# STM32F103xx_LQFP48.net
KiCad netlist of a schematic drawn in Altium Designer
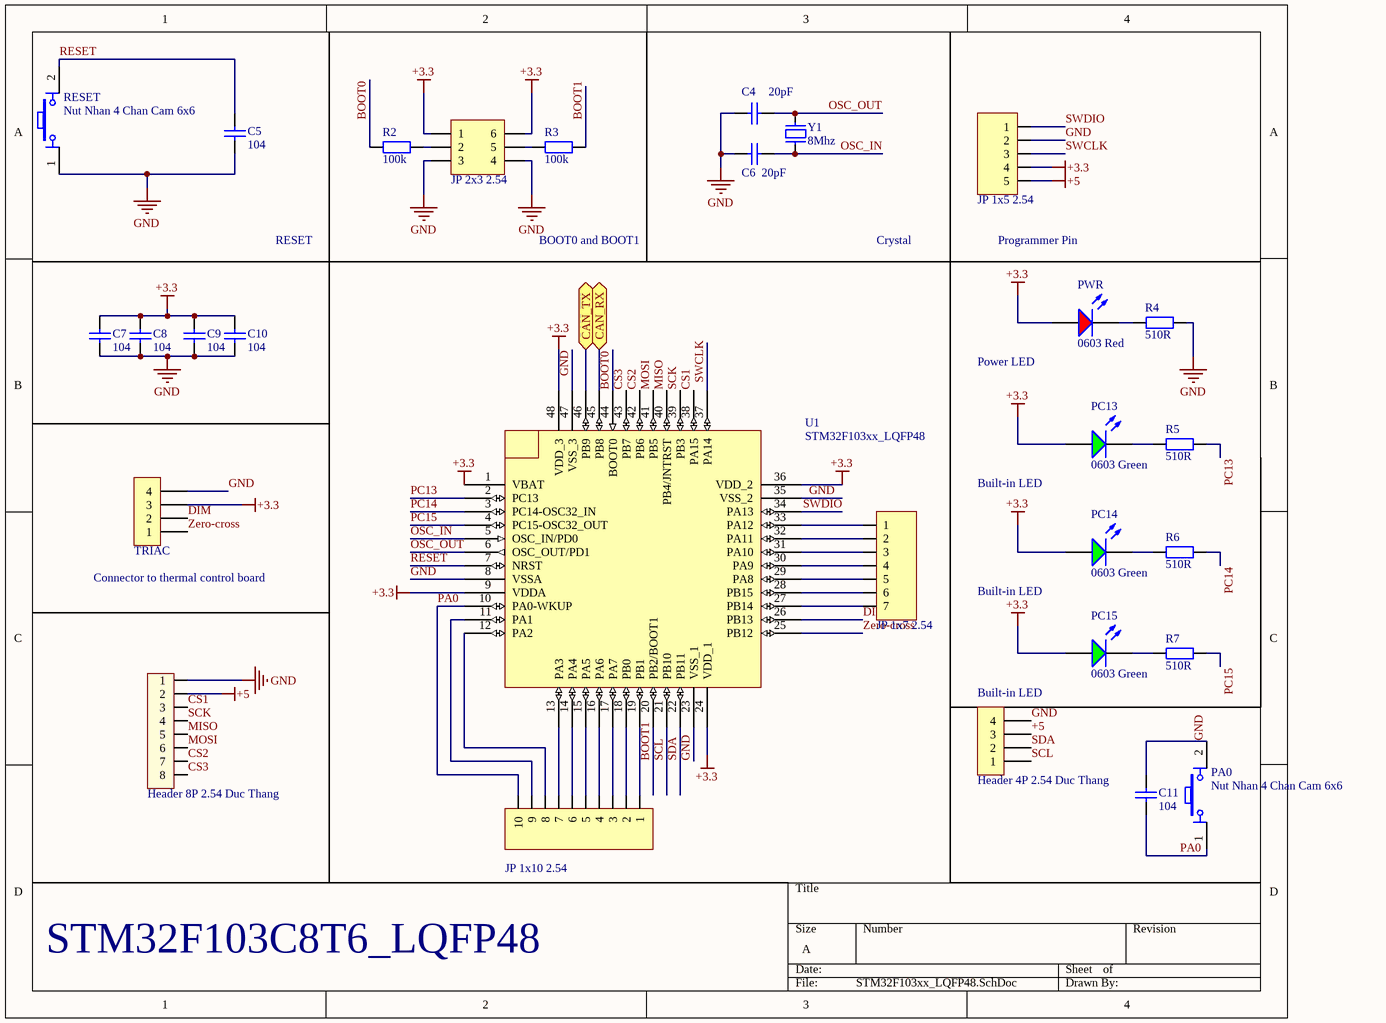
[diagram p0: STM32F103xx_LQFP48.SchDoc]

(export (version "E")
  (design (tool "Eeschema 10.0.6"))
  (components
    (comp (ref "C4")
      (value "20pF")
      (footprint "tu 0603")
      (description "Dán")
      (libsource (lib "Altium_Lib_by_KhueNguyenCreator") (part "Tu 0603 22pF 50V 10%"))
    )
    (comp (ref "C5")
      (value "104")
      (footprint "tu 0603")
      (description "Dán")
      (libsource (lib "Altium_Lib_by_KhueNguyenCreator") (part "Tu 0603 104 50V 10%"))
    )
    (comp (ref "C6")
      (value "20pF")
      (footprint "tu 0603")
      (description "Dán")
      (libsource (lib "Altium_Lib_by_KhueNguyenCreator") (part "Tu 0603 22pF 50V 10%"))
    )
    (comp (ref "C7")
      (value "104")
      (footprint "tu 0603")
      (description "Dán")
      (libsource (lib "Altium_Lib_by_KhueNguyenCreator") (part "Tu 0603 104 50V 10%"))
    )
    (comp (ref "C8")
      (value "104")
      (footprint "tu 0603")
      (description "Dán")
      (libsource (lib "Altium_Lib_by_KhueNguyenCreator") (part "Tu 0603 104 50V 10%"))
    )
    (comp (ref "C9")
      (value "104")
      (footprint "tu 0603")
      (description "Dán")
      (libsource (lib "Altium_Lib_by_KhueNguyenCreator") (part "Tu 0603 104 50V 10%"))
    )
    (comp (ref "C10")
      (value "104")
      (footprint "tu 0603")
      (description "Dán")
      (libsource (lib "Altium_Lib_by_KhueNguyenCreator") (part "Tu 0603 104 50V 10%"))
    )
    (comp (ref "C11")
      (value "104")
      (footprint "tu 0603")
      (description "Dán")
      (libsource (lib "Altium_Lib_by_KhueNguyenCreator") (part "Tu 0603 104 50V 10%"))
    )
    (comp (ref "H3")
      (value "TRIAC")
      (footprint "XH2.54M-4")
      (description "Cắm")
      (libsource (lib "Altium_Lib_by_KhueNguyenCreator") (part "Header 4P 2.54 Duc Thang"))
    )
    (comp (ref "H4")
      (value "Header 8P 2.54 Duc Thang")
      (footprint "XH2.54M-8")
      (description "Cắm")
      (libsource (lib "Altium_Lib_by_KhueNguyenCreator") (part "Header 8P 2.54 Duc Thang"))
    )
    (comp (ref "H5")
      (value "Header 4P 2.54 Duc Thang")
      (footprint "XH2.54M-4")
      (description "Cắm")
      (libsource (lib "Altium_Lib_by_KhueNguyenCreator") (part "Header 4P 2.54 Duc Thang"))
    )
    (comp (ref "JP2")
      (value "JP 1x5 2.54")
      (footprint "JP 1x5 DC")
      (description "Cắm")
      (libsource (lib "Altium_Lib_by_KhueNguyenCreator") (part "JP 1x5 2.54 Duc Cong"))
    )
    (comp (ref "JP3")
      (value "JP 2x3 2.54")
      (footprint "JP 2x3 DT")
      (description "Cắm")
      (libsource (lib "Altium_Lib_by_KhueNguyenCreator") (part "JP 2x3 2.54 Duc Thang"))
    )
    (comp (ref "JP4")
      (value "JP 1x7 2.54")
      (footprint "JP 1x7 DT")
      (description "Cắm")
      (libsource (lib "Altium_Lib_by_KhueNguyenCreator") (part "JP 1x7 2.54 Duc Thang"))
    )
    (comp (ref "JP5")
      (value "JP 1x10 2.54")
      (footprint "JP 1x10 DT")
      (description "Cắm")
      (libsource (lib "Altium_Lib_by_KhueNguyenCreator") (part "JP 1x10 2.54 Duc Thang"))
    )
    (comp (ref "PA0")
      (value "Nut Nhan 4 Chan Cam 6x6")
      (footprint "Nut Nhan 4 Chan Cam 6x6")
      (description "Nut Nhan 4 Chan 6x6mm")
      (libsource (lib "Altium_Lib_by_KhueNguyenCreator") (part "Nut Nhan 4 Chan Cam 6x6"))
    )
    (comp (ref "PC13")
      (value "0603 Green")
      (footprint "0603_LED_S1")
      (description "LED")
      (libsource (lib "Miscellaneous Devices LC") (part "0603 LED Green"))
    )
    (comp (ref "PC14")
      (value "0603 Green")
      (footprint "0603_LED_S1")
      (description "LED")
      (libsource (lib "Miscellaneous Devices LC") (part "0603 LED Green"))
    )
    (comp (ref "PC15")
      (value "0603 Green")
      (footprint "0603_LED_S1")
      (description "LED")
      (libsource (lib "Miscellaneous Devices LC") (part "0603 LED Green"))
    )
    (comp (ref "PWR")
      (value "0603 Red")
      (footprint "0603_LED_S1")
      (description "LED")
      (libsource (lib "Miscellaneous Devices LC") (part "0603 LED Red"))
    )
    (comp (ref "R2")
      (value "100k")
      (footprint "tro smd 0603")
      (description "Dán")
      (libsource (lib "Altium_Lib_by_KhueNguyenCreator") (part "Tro 0603 1% 10k"))
    )
    (comp (ref "R3")
      (value "100k")
      (footprint "tro smd 0603")
      (description "Dán")
      (libsource (lib "Altium_Lib_by_KhueNguyenCreator") (part "Tro 0603 1% 10k"))
    )
    (comp (ref "R4")
      (value "510R")
      (footprint "tro smd 0603")
      (description "Dán")
      (libsource (lib "Altium_Lib_by_KhueNguyenCreator") (part "Tro 0603 1% 10k"))
    )
    (comp (ref "R5")
      (value "510R")
      (footprint "tro smd 0603")
      (description "Dán")
      (libsource (lib "Altium_Lib_by_KhueNguyenCreator") (part "Tro 0603 1% 10k"))
    )
    (comp (ref "R6")
      (value "510R")
      (footprint "tro smd 0603")
      (description "Dán")
      (libsource (lib "Altium_Lib_by_KhueNguyenCreator") (part "Tro 0603 1% 10k"))
    )
    (comp (ref "R7")
      (value "510R")
      (footprint "tro smd 0603")
      (description "Dán")
      (libsource (lib "Altium_Lib_by_KhueNguyenCreator") (part "Tro 0603 1% 10k"))
    )
    (comp (ref "RESET")
      (value "Nut Nhan 4 Chan Cam 6x6")
      (footprint "Nut Nhan 4 Chan Cam 6x6")
      (description "Nut Nhan 4 Chan 6x6mm")
      (libsource (lib "Altium_Lib_by_KhueNguyenCreator") (part "Nut Nhan 4 Chan Cam 6x6"))
    )
    (comp (ref "U1")
      (value "STM32F103xx_LQFP48")
      (footprint "STM32_LQPF48")
      (fields (field (name "PUBLISHER") "Altium Limited"))
      (libsource (lib "Altium_Lib_by_KhueNguyenCreator") (part "STM32F103xx_LQFP48"))
    )
    (comp (ref "Y1")
      (value "8Mhz")
      (footprint "Thach Anh 2 chan cam")
      (description "Crystal For all Crystal 2pin.")
      (libsource (lib "Altium_Lib_by_KhueNguyenCreator") (part "Thach Anh 2 chan Cam"))
    )
  )
  (nets
    (net (code "1") (name "+3.3") (class "Default")
      (node (ref "C10") (pin "1") (pinfunction "1_1") (pintype "passive"))
      (node (ref "C7") (pin "1") (pinfunction "1_1") (pintype "passive"))
      (node (ref "C8") (pin "1") (pinfunction "1_1") (pintype "passive"))
      (node (ref "C9") (pin "1") (pinfunction "1_1") (pintype "passive"))
      (node (ref "H3") (pin "3") (pinfunction "3_3") (pintype "passive"))
      (node (ref "JP2") (pin "4") (pinfunction "4_4") (pintype "passive"))
      (node (ref "JP3") (pin "1") (pinfunction "1_1") (pintype "passive"))
      (node (ref "JP3") (pin "6") (pinfunction "6_6") (pintype "passive"))
      (node (ref "PC13") (pin "A") (pinfunction "A_A") (pintype "passive"))
      (node (ref "PC14") (pin "A") (pinfunction "A_A") (pintype "passive"))
      (node (ref "PC15") (pin "A") (pinfunction "A_A") (pintype "passive"))
      (node (ref "PWR") (pin "A") (pinfunction "A_A") (pintype "passive"))
      (node (ref "U1") (pin "1") (pinfunction "VBAT_1") (pintype "power_in"))
      (node (ref "U1") (pin "24") (pinfunction "VDD_1_24") (pintype "power_in"))
      (node (ref "U1") (pin "36") (pinfunction "VDD_2_36") (pintype "power_in"))
      (node (ref "U1") (pin "48") (pinfunction "VDD_3_48") (pintype "power_in"))
      (node (ref "U1") (pin "9") (pinfunction "VDDA_9") (pintype "power_in"))
    )
    (net (code "2") (name "+5") (class "Default")
      (node (ref "H4") (pin "2") (pinfunction "2_2") (pintype "passive"))
      (node (ref "H5") (pin "3") (pinfunction "3_3") (pintype "passive"))
      (node (ref "JP2") (pin "5") (pinfunction "5_5") (pintype "passive"))
    )
    (net (code "3") (name "/BOOT0") (class "Default")
      (node (ref "R2") (pin "1") (pinfunction "1_1") (pintype "passive"))
      (node (ref "U1") (pin "44") (pinfunction "BOOT0_44") (pintype "input"))
    )
    (net (code "4") (name "/BOOT1") (class "Default")
      (node (ref "R3") (pin "2") (pinfunction "2_2") (pintype "passive"))
      (node (ref "U1") (pin "20") (pinfunction "PB2/BOOT1_20") (pintype "bidirectional"))
    )
    (net (code "5") (name "/CAN_RX") (class "Default")
      (node (ref "U1") (pin "45") (pinfunction "PB8_45") (pintype "bidirectional"))
    )
    (net (code "6") (name "/CAN_TX") (class "Default")
      (node (ref "U1") (pin "46") (pinfunction "PB9_46") (pintype "bidirectional"))
    )
    (net (code "7") (name "/CS1") (class "Default")
      (node (ref "H4") (pin "3") (pinfunction "3_3") (pintype "passive"))
      (node (ref "U1") (pin "38") (pinfunction "PA15_38") (pintype "bidirectional"))
    )
    (net (code "8") (name "/CS2") (class "Default")
      (node (ref "H4") (pin "7") (pinfunction "7_7") (pintype "passive"))
      (node (ref "U1") (pin "42") (pinfunction "PB6_42") (pintype "bidirectional"))
    )
    (net (code "9") (name "/CS3") (class "Default")
      (node (ref "H4") (pin "8") (pinfunction "8_8") (pintype "passive"))
      (node (ref "U1") (pin "43") (pinfunction "PB7_43") (pintype "bidirectional"))
    )
    (net (code "10") (name "/DIM") (class "Default")
      (node (ref "H3") (pin "2") (pinfunction "2_2") (pintype "passive"))
      (node (ref "U1") (pin "26") (pinfunction "PB13_26") (pintype "bidirectional"))
    )
    (net (code "11") (name "/MISO") (class "Default")
      (node (ref "H4") (pin "5") (pinfunction "5_5") (pintype "passive"))
      (node (ref "U1") (pin "40") (pinfunction "PB4/JNTRST_40") (pintype "bidirectional"))
    )
    (net (code "12") (name "/MOSI") (class "Default")
      (node (ref "H4") (pin "6") (pinfunction "6_6") (pintype "passive"))
      (node (ref "U1") (pin "41") (pinfunction "PB5_41") (pintype "bidirectional"))
    )
    (net (code "13") (name "/OSC_IN") (class "Default")
      (node (ref "C6") (pin "1") (pinfunction "1_1") (pintype "passive"))
      (node (ref "U1") (pin "5") (pinfunction "OSC_IN/PD0_5") (pintype "input"))
      (node (ref "Y1") (pin "1") (pinfunction "1_1") (pintype "passive"))
    )
    (net (code "14") (name "/OSC_OUT") (class "Default")
      (node (ref "C4") (pin "1") (pinfunction "1_1") (pintype "passive"))
      (node (ref "U1") (pin "6") (pinfunction "OSC_OUT/PD1_6") (pintype "output"))
      (node (ref "Y1") (pin "2") (pinfunction "2_2") (pintype "passive"))
    )
    (net (code "15") (name "/PA0") (class "Default")
      (node (ref "C11") (pin "1") (pinfunction "1_1") (pintype "passive"))
      (node (ref "JP5") (pin "10") (pinfunction "10_10") (pintype "passive"))
      (node (ref "PA0") (pin "1") (pintype "passive"))
      (node (ref "U1") (pin "10") (pinfunction "PA0-WKUP_10") (pintype "bidirectional"))
    )
    (net (code "16") (name "/PC13") (class "Default")
      (node (ref "R5") (pin "1") (pinfunction "1_1") (pintype "passive"))
      (node (ref "U1") (pin "2") (pinfunction "PC13_2") (pintype "bidirectional"))
    )
    (net (code "17") (name "/PC14") (class "Default")
      (node (ref "R6") (pin "1") (pinfunction "1_1") (pintype "passive"))
      (node (ref "U1") (pin "3") (pinfunction "PC14-OSC32_IN_3") (pintype "bidirectional"))
    )
    (net (code "18") (name "/PC15") (class "Default")
      (node (ref "R7") (pin "1") (pinfunction "1_1") (pintype "passive"))
      (node (ref "U1") (pin "4") (pinfunction "PC15-OSC32_OUT_4") (pintype "bidirectional"))
    )
    (net (code "19") (name "/RESET") (class "Default")
      (node (ref "C5") (pin "1") (pinfunction "1_1") (pintype "passive"))
      (node (ref "RESET") (pin "2") (pintype "passive"))
      (node (ref "U1") (pin "7") (pinfunction "NRST_7") (pintype "bidirectional"))
    )
    (net (code "20") (name "/SCK") (class "Default")
      (node (ref "H4") (pin "4") (pinfunction "4_4") (pintype "passive"))
      (node (ref "U1") (pin "39") (pinfunction "PB3_39") (pintype "bidirectional"))
    )
    (net (code "21") (name "/SCL") (class "Default")
      (node (ref "H5") (pin "1") (pinfunction "1_1") (pintype "passive"))
      (node (ref "U1") (pin "21") (pinfunction "PB10_21") (pintype "bidirectional"))
    )
    (net (code "22") (name "/SDA") (class "Default")
      (node (ref "H5") (pin "2") (pinfunction "2_2") (pintype "passive"))
      (node (ref "U1") (pin "22") (pinfunction "PB11_22") (pintype "bidirectional"))
    )
    (net (code "23") (name "/SWCLK") (class "Default")
      (node (ref "JP2") (pin "3") (pinfunction "3_3") (pintype "passive"))
      (node (ref "U1") (pin "37") (pinfunction "PA14_37") (pintype "bidirectional"))
    )
    (net (code "24") (name "/SWDIO") (class "Default")
      (node (ref "JP2") (pin "1") (pinfunction "1_1") (pintype "passive"))
      (node (ref "U1") (pin "34") (pinfunction "PA13_34") (pintype "bidirectional"))
    )
    (net (code "25") (name "/Zero-cross") (class "Default")
      (node (ref "H3") (pin "1") (pinfunction "1_1") (pintype "passive"))
      (node (ref "U1") (pin "25") (pinfunction "PB12_25") (pintype "bidirectional"))
    )
    (net (code "26") (name "GND") (class "Default")
      (node (ref "C10") (pin "2") (pinfunction "2_2") (pintype "passive"))
      (node (ref "C11") (pin "2") (pinfunction "2_2") (pintype "passive"))
      (node (ref "C4") (pin "2") (pinfunction "2_2") (pintype "passive"))
      (node (ref "C5") (pin "2") (pinfunction "2_2") (pintype "passive"))
      (node (ref "C6") (pin "2") (pinfunction "2_2") (pintype "passive"))
      (node (ref "C7") (pin "2") (pinfunction "2_2") (pintype "passive"))
      (node (ref "C8") (pin "2") (pinfunction "2_2") (pintype "passive"))
      (node (ref "C9") (pin "2") (pinfunction "2_2") (pintype "passive"))
      (node (ref "H3") (pin "4") (pinfunction "4_4") (pintype "passive"))
      (node (ref "H4") (pin "1") (pinfunction "1_1") (pintype "passive"))
      (node (ref "H5") (pin "4") (pinfunction "4_4") (pintype "passive"))
      (node (ref "JP2") (pin "2") (pinfunction "2_2") (pintype "passive"))
      (node (ref "JP3") (pin "3") (pinfunction "3_3") (pintype "passive"))
      (node (ref "JP3") (pin "4") (pinfunction "4_4") (pintype "passive"))
      (node (ref "PA0") (pin "2") (pintype "passive"))
      (node (ref "R4") (pin "1") (pinfunction "1_1") (pintype "passive"))
      (node (ref "RESET") (pin "1") (pintype "passive"))
      (node (ref "U1") (pin "23") (pinfunction "VSS_1_23") (pintype "power_in"))
      (node (ref "U1") (pin "35") (pinfunction "VSS_2_35") (pintype "power_in"))
      (node (ref "U1") (pin "47") (pinfunction "VSS_3_47") (pintype "power_in"))
      (node (ref "U1") (pin "8") (pinfunction "VSSA_8") (pintype "power_in"))
    )
    (net (code "27") (name "Net-(JP3-Pad2)") (class "Default")
      (node (ref "JP3") (pin "2") (pinfunction "2_2") (pintype "passive"))
      (node (ref "R2") (pin "2") (pinfunction "2_2") (pintype "passive"))
    )
    (net (code "28") (name "Net-(JP3-Pad5)") (class "Default")
      (node (ref "JP3") (pin "5") (pinfunction "5_5") (pintype "passive"))
      (node (ref "R3") (pin "1") (pinfunction "1_1") (pintype "passive"))
    )
    (net (code "29") (name "Net-(PC13-PadK)") (class "Default")
      (node (ref "PC13") (pin "K") (pinfunction "K_K") (pintype "passive"))
      (node (ref "R5") (pin "2") (pinfunction "2_2") (pintype "passive"))
    )
    (net (code "30") (name "Net-(PC14-PadK)") (class "Default")
      (node (ref "PC14") (pin "K") (pinfunction "K_K") (pintype "passive"))
      (node (ref "R6") (pin "2") (pinfunction "2_2") (pintype "passive"))
    )
    (net (code "31") (name "Net-(PC15-PadK)") (class "Default")
      (node (ref "PC15") (pin "K") (pinfunction "K_K") (pintype "passive"))
      (node (ref "R7") (pin "2") (pinfunction "2_2") (pintype "passive"))
    )
    (net (code "32") (name "Net-(PWR-PadK)") (class "Default")
      (node (ref "PWR") (pin "K") (pinfunction "K_K") (pintype "passive"))
      (node (ref "R4") (pin "2") (pinfunction "2_2") (pintype "passive"))
    )
    (net (code "33") (name "Net-(U1-PA1)") (class "Default")
      (node (ref "JP5") (pin "9") (pinfunction "9_9") (pintype "passive"))
      (node (ref "U1") (pin "11") (pinfunction "PA1_11") (pintype "bidirectional"))
    )
    (net (code "34") (name "Net-(U1-PA2)") (class "Default")
      (node (ref "JP5") (pin "8") (pinfunction "8_8") (pintype "passive"))
      (node (ref "U1") (pin "12") (pinfunction "PA2_12") (pintype "bidirectional"))
    )
    (net (code "35") (name "Net-(U1-PA3)") (class "Default")
      (node (ref "JP5") (pin "7") (pinfunction "7_7") (pintype "passive"))
      (node (ref "U1") (pin "13") (pinfunction "PA3_13") (pintype "bidirectional"))
    )
    (net (code "36") (name "Net-(U1-PA4)") (class "Default")
      (node (ref "JP5") (pin "6") (pinfunction "6_6") (pintype "passive"))
      (node (ref "U1") (pin "14") (pinfunction "PA4_14") (pintype "bidirectional"))
    )
    (net (code "37") (name "Net-(U1-PA5)") (class "Default")
      (node (ref "JP5") (pin "5") (pinfunction "5_5") (pintype "passive"))
      (node (ref "U1") (pin "15") (pinfunction "PA5_15") (pintype "bidirectional"))
    )
    (net (code "38") (name "Net-(U1-PA6)") (class "Default")
      (node (ref "JP5") (pin "4") (pinfunction "4_4") (pintype "passive"))
      (node (ref "U1") (pin "16") (pinfunction "PA6_16") (pintype "bidirectional"))
    )
    (net (code "39") (name "Net-(U1-PA7)") (class "Default")
      (node (ref "JP5") (pin "3") (pinfunction "3_3") (pintype "passive"))
      (node (ref "U1") (pin "17") (pinfunction "PA7_17") (pintype "bidirectional"))
    )
    (net (code "40") (name "Net-(U1-PA8)") (class "Default")
      (node (ref "JP4") (pin "5") (pinfunction "5_5") (pintype "passive"))
      (node (ref "U1") (pin "29") (pinfunction "PA8_29") (pintype "bidirectional"))
    )
    (net (code "41") (name "Net-(U1-PA9)") (class "Default")
      (node (ref "JP4") (pin "4") (pinfunction "4_4") (pintype "passive"))
      (node (ref "U1") (pin "30") (pinfunction "PA9_30") (pintype "bidirectional"))
    )
    (net (code "42") (name "Net-(U1-PA10)") (class "Default")
      (node (ref "JP4") (pin "3") (pinfunction "3_3") (pintype "passive"))
      (node (ref "U1") (pin "31") (pinfunction "PA10_31") (pintype "bidirectional"))
    )
    (net (code "43") (name "Net-(U1-PA11)") (class "Default")
      (node (ref "JP4") (pin "2") (pinfunction "2_2") (pintype "passive"))
      (node (ref "U1") (pin "32") (pinfunction "PA11_32") (pintype "bidirectional"))
    )
    (net (code "44") (name "Net-(U1-PA12)") (class "Default")
      (node (ref "JP4") (pin "1") (pinfunction "1_1") (pintype "passive"))
      (node (ref "U1") (pin "33") (pinfunction "PA12_33") (pintype "bidirectional"))
    )
    (net (code "45") (name "Net-(U1-PB0)") (class "Default")
      (node (ref "JP5") (pin "2") (pinfunction "2_2") (pintype "passive"))
      (node (ref "U1") (pin "18") (pinfunction "PB0_18") (pintype "bidirectional"))
    )
    (net (code "46") (name "Net-(U1-PB1)") (class "Default")
      (node (ref "JP5") (pin "1") (pinfunction "1_1") (pintype "passive"))
      (node (ref "U1") (pin "19") (pinfunction "PB1_19") (pintype "bidirectional"))
    )
    (net (code "47") (name "Net-(U1-PB14)") (class "Default")
      (node (ref "JP4") (pin "7") (pinfunction "7_7") (pintype "passive"))
      (node (ref "U1") (pin "27") (pinfunction "PB14_27") (pintype "bidirectional"))
    )
    (net (code "48") (name "Net-(U1-PB15)") (class "Default")
      (node (ref "JP4") (pin "6") (pinfunction "6_6") (pintype "passive"))
      (node (ref "U1") (pin "28") (pinfunction "PB15_28") (pintype "bidirectional"))
    )
  )
)
